# TopAdapter.net
KiCad netlist of a schematic drawn in Altium Designer
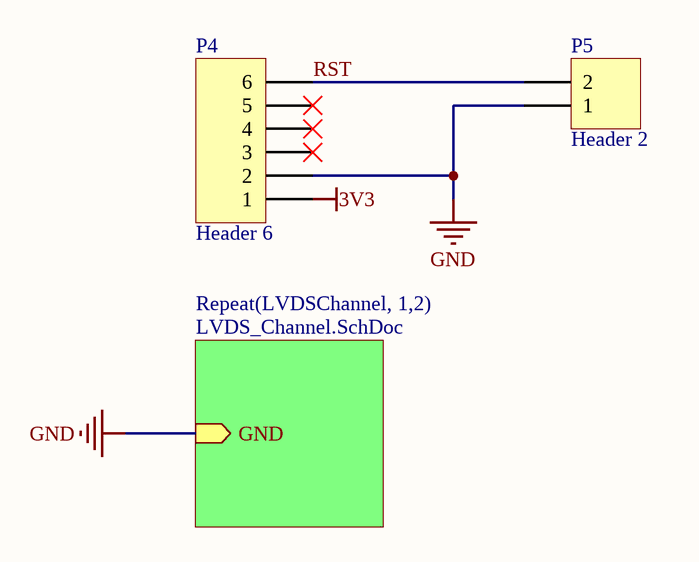
[diagram p0: TopAdapter.SchDoc]

(export (version "E")
  (design (tool "Eeschema 10.0.6"))
  (components
    (comp (ref "P4")
      (value "Header 6")
      (footprint "HDR1X6")
      (description "Header, 6-Pin")
      (fields (field (name "PUBLISHER") "Altium Limited"))
      (libsource (lib "Miscellaneous Connectors") (part "Header 6"))
    )
    (comp (ref "P5")
      (value "Header 2")
      (footprint "HDR1X2")
      (description "Header, 2-Pin")
      (fields (field (name "PUBLISHER") "Altium Limited"))
      (libsource (lib "Miscellaneous Connectors") (part "Header 2"))
    )
  )
  (nets
    (net (code "1") (name "/RST") (class "Default")
      (node (ref "P4") (pin "6") (pinfunction "6_6") (pintype "passive"))
      (node (ref "P5") (pin "2") (pinfunction "2_2") (pintype "passive"))
    )
    (net (code "2") (name "3V3") (class "Default")
      (node (ref "P4") (pin "1") (pinfunction "1_1") (pintype "passive"))
    )
    (net (code "3") (name "GND") (class "Default")
      (node (ref "P4") (pin "2") (pinfunction "2_2") (pintype "passive"))
      (node (ref "P5") (pin "1") (pinfunction "1_1") (pintype "passive"))
    )
    (net (code "4") (name "unconnected-(P4-Pad3)") (class "Default")
      (node (ref "P4") (pin "3") (pinfunction "3_3") (pintype "passive+no_connect"))
    )
    (net (code "5") (name "unconnected-(P4-Pad4)") (class "Default")
      (node (ref "P4") (pin "4") (pinfunction "4_4") (pintype "passive+no_connect"))
    )
    (net (code "6") (name "unconnected-(P4-Pad5)") (class "Default")
      (node (ref "P4") (pin "5") (pinfunction "5_5") (pintype "passive+no_connect"))
    )
  )
)
